# KEYPAD.net
KiCad netlist of a schematic drawn in Altium Designer
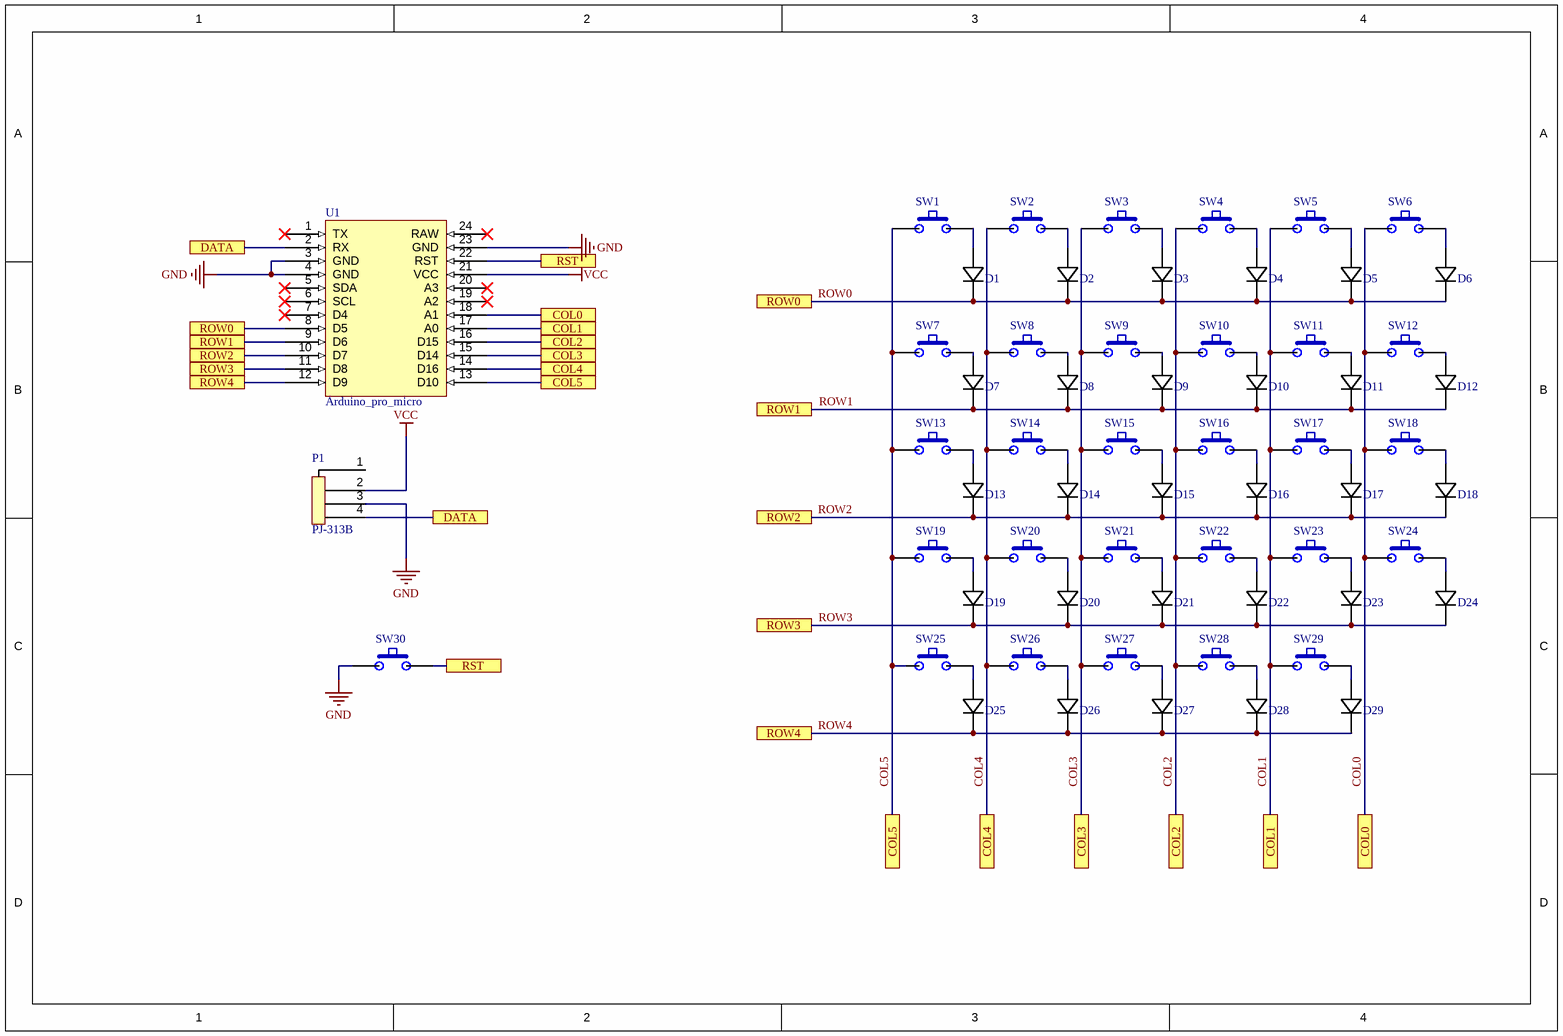
[diagram p0: KEYPAD.SchDoc]

(export (version "E")
  (design (tool "Eeschema 10.0.6"))
  (components
    (comp (ref "D1")
      (value "1N4148WSF-7")
      (footprint "DIOAD829W49L456D191")
      (description "No Description Available")
      (fields (field (name "COPYRIGHT") "Copyright (C) 2021 Ultra Librarian. All rights reserved."))
      (libsource (lib "lib") (part "1N4148WSF-7"))
    )
    (comp (ref "D2")
      (value "1N4148WSF-7")
      (footprint "DIOAD829W49L456D191")
      (description "No Description Available")
      (fields (field (name "COPYRIGHT") "Copyright (C) 2021 Ultra Librarian. All rights reserved."))
      (libsource (lib "lib") (part "1N4148WSF-7"))
    )
    (comp (ref "D3")
      (value "1N4148WSF-7")
      (footprint "DIOAD829W49L456D191")
      (description "No Description Available")
      (fields (field (name "COPYRIGHT") "Copyright (C) 2021 Ultra Librarian. All rights reserved."))
      (libsource (lib "lib") (part "1N4148WSF-7"))
    )
    (comp (ref "D4")
      (value "1N4148WSF-7")
      (footprint "DIOAD829W49L456D191")
      (description "No Description Available")
      (fields (field (name "COPYRIGHT") "Copyright (C) 2021 Ultra Librarian. All rights reserved."))
      (libsource (lib "lib") (part "1N4148WSF-7"))
    )
    (comp (ref "D5")
      (value "1N4148WSF-7")
      (footprint "DIOAD829W49L456D191")
      (description "No Description Available")
      (fields (field (name "COPYRIGHT") "Copyright (C) 2021 Ultra Librarian. All rights reserved."))
      (libsource (lib "lib") (part "1N4148WSF-7"))
    )
    (comp (ref "D6")
      (value "1N4148WSF-7")
      (footprint "DIOAD829W49L456D191")
      (description "No Description Available")
      (fields (field (name "COPYRIGHT") "Copyright (C) 2021 Ultra Librarian. All rights reserved."))
      (libsource (lib "lib") (part "1N4148WSF-7"))
    )
    (comp (ref "D7")
      (value "1N4148WSF-7")
      (footprint "DIOAD829W49L456D191")
      (description "No Description Available")
      (fields (field (name "COPYRIGHT") "Copyright (C) 2021 Ultra Librarian. All rights reserved."))
      (libsource (lib "lib") (part "1N4148WSF-7"))
    )
    (comp (ref "D8")
      (value "1N4148WSF-7")
      (footprint "DIOAD829W49L456D191")
      (description "No Description Available")
      (fields (field (name "COPYRIGHT") "Copyright (C) 2021 Ultra Librarian. All rights reserved."))
      (libsource (lib "lib") (part "1N4148WSF-7"))
    )
    (comp (ref "D9")
      (value "1N4148WSF-7")
      (footprint "DIOAD829W49L456D191")
      (description "No Description Available")
      (fields (field (name "COPYRIGHT") "Copyright (C) 2021 Ultra Librarian. All rights reserved."))
      (libsource (lib "lib") (part "1N4148WSF-7"))
    )
    (comp (ref "D10")
      (value "1N4148WSF-7")
      (footprint "DIOAD829W49L456D191")
      (description "No Description Available")
      (fields (field (name "COPYRIGHT") "Copyright (C) 2021 Ultra Librarian. All rights reserved."))
      (libsource (lib "lib") (part "1N4148WSF-7"))
    )
    (comp (ref "D11")
      (value "1N4148WSF-7")
      (footprint "DIOAD829W49L456D191")
      (description "No Description Available")
      (fields (field (name "COPYRIGHT") "Copyright (C) 2021 Ultra Librarian. All rights reserved."))
      (libsource (lib "lib") (part "1N4148WSF-7"))
    )
    (comp (ref "D12")
      (value "1N4148WSF-7")
      (footprint "DIOAD829W49L456D191")
      (description "No Description Available")
      (fields (field (name "COPYRIGHT") "Copyright (C) 2021 Ultra Librarian. All rights reserved."))
      (libsource (lib "lib") (part "1N4148WSF-7"))
    )
    (comp (ref "D13")
      (value "1N4148WSF-7")
      (footprint "DIOAD829W49L456D191")
      (description "No Description Available")
      (fields (field (name "COPYRIGHT") "Copyright (C) 2021 Ultra Librarian. All rights reserved."))
      (libsource (lib "lib") (part "1N4148WSF-7"))
    )
    (comp (ref "D14")
      (value "1N4148WSF-7")
      (footprint "DIOAD829W49L456D191")
      (description "No Description Available")
      (fields (field (name "COPYRIGHT") "Copyright (C) 2021 Ultra Librarian. All rights reserved."))
      (libsource (lib "lib") (part "1N4148WSF-7"))
    )
    (comp (ref "D15")
      (value "1N4148WSF-7")
      (footprint "DIOAD829W49L456D191")
      (description "No Description Available")
      (fields (field (name "COPYRIGHT") "Copyright (C) 2021 Ultra Librarian. All rights reserved."))
      (libsource (lib "lib") (part "1N4148WSF-7"))
    )
    (comp (ref "D16")
      (value "1N4148WSF-7")
      (footprint "DIOAD829W49L456D191")
      (description "No Description Available")
      (fields (field (name "COPYRIGHT") "Copyright (C) 2021 Ultra Librarian. All rights reserved."))
      (libsource (lib "lib") (part "1N4148WSF-7"))
    )
    (comp (ref "D17")
      (value "1N4148WSF-7")
      (footprint "DIOAD829W49L456D191")
      (description "No Description Available")
      (fields (field (name "COPYRIGHT") "Copyright (C) 2021 Ultra Librarian. All rights reserved."))
      (libsource (lib "lib") (part "1N4148WSF-7"))
    )
    (comp (ref "D18")
      (value "1N4148WSF-7")
      (footprint "DIOAD829W49L456D191")
      (description "No Description Available")
      (fields (field (name "COPYRIGHT") "Copyright (C) 2021 Ultra Librarian. All rights reserved."))
      (libsource (lib "lib") (part "1N4148WSF-7"))
    )
    (comp (ref "D19")
      (value "1N4148WSF-7")
      (footprint "DIOAD829W49L456D191")
      (description "No Description Available")
      (fields (field (name "COPYRIGHT") "Copyright (C) 2021 Ultra Librarian. All rights reserved."))
      (libsource (lib "lib") (part "1N4148WSF-7"))
    )
    (comp (ref "D20")
      (value "1N4148WSF-7")
      (footprint "DIOAD829W49L456D191")
      (description "No Description Available")
      (fields (field (name "COPYRIGHT") "Copyright (C) 2021 Ultra Librarian. All rights reserved."))
      (libsource (lib "lib") (part "1N4148WSF-7"))
    )
    (comp (ref "D21")
      (value "1N4148WSF-7")
      (footprint "DIOAD829W49L456D191")
      (description "No Description Available")
      (fields (field (name "COPYRIGHT") "Copyright (C) 2021 Ultra Librarian. All rights reserved."))
      (libsource (lib "lib") (part "1N4148WSF-7"))
    )
    (comp (ref "D22")
      (value "1N4148WSF-7")
      (footprint "DIOAD829W49L456D191")
      (description "No Description Available")
      (fields (field (name "COPYRIGHT") "Copyright (C) 2021 Ultra Librarian. All rights reserved."))
      (libsource (lib "lib") (part "1N4148WSF-7"))
    )
    (comp (ref "D23")
      (value "1N4148WSF-7")
      (footprint "DIOAD829W49L456D191")
      (description "No Description Available")
      (fields (field (name "COPYRIGHT") "Copyright (C) 2021 Ultra Librarian. All rights reserved."))
      (libsource (lib "lib") (part "1N4148WSF-7"))
    )
    (comp (ref "D24")
      (value "1N4148WSF-7")
      (footprint "DIOAD829W49L456D191")
      (description "No Description Available")
      (fields (field (name "COPYRIGHT") "Copyright (C) 2021 Ultra Librarian. All rights reserved."))
      (libsource (lib "lib") (part "1N4148WSF-7"))
    )
    (comp (ref "D25")
      (value "1N4148WSF-7")
      (footprint "DIOAD829W49L456D191")
      (description "No Description Available")
      (fields (field (name "COPYRIGHT") "Copyright (C) 2021 Ultra Librarian. All rights reserved."))
      (libsource (lib "lib") (part "1N4148WSF-7"))
    )
    (comp (ref "D26")
      (value "1N4148WSF-7")
      (footprint "DIOAD829W49L456D191")
      (description "No Description Available")
      (fields (field (name "COPYRIGHT") "Copyright (C) 2021 Ultra Librarian. All rights reserved."))
      (libsource (lib "lib") (part "1N4148WSF-7"))
    )
    (comp (ref "D27")
      (value "1N4148WSF-7")
      (footprint "DIOAD829W49L456D191")
      (description "No Description Available")
      (fields (field (name "COPYRIGHT") "Copyright (C) 2021 Ultra Librarian. All rights reserved."))
      (libsource (lib "lib") (part "1N4148WSF-7"))
    )
    (comp (ref "D28")
      (value "1N4148WSF-7")
      (footprint "DIOAD829W49L456D191")
      (description "No Description Available")
      (fields (field (name "COPYRIGHT") "Copyright (C) 2021 Ultra Librarian. All rights reserved."))
      (libsource (lib "lib") (part "1N4148WSF-7"))
    )
    (comp (ref "D29")
      (value "1N4148WSF-7")
      (footprint "DIOAD829W49L456D191")
      (description "No Description Available")
      (fields (field (name "COPYRIGHT") "Copyright (C) 2021 Ultra Librarian. All rights reserved."))
      (libsource (lib "lib") (part "1N4148WSF-7"))
    )
    (comp (ref "P1") (value "PJ-313B") (footprint "pj-313b6-x") (libsource (lib "lib") (part "PJ-313B")))
    (comp (ref "SW1") (value "~") (footprint "cherry_sw_double_side") (libsource (lib "lib") (part "SW")))
    (comp (ref "SW2") (value "~") (footprint "cherry_sw_double_side") (libsource (lib "lib") (part "SW")))
    (comp (ref "SW3") (value "~") (footprint "cherry_sw_double_side") (libsource (lib "lib") (part "SW")))
    (comp (ref "SW4") (value "~") (footprint "cherry_sw_double_side") (libsource (lib "lib") (part "SW")))
    (comp (ref "SW5") (value "~") (footprint "cherry_sw_double_side") (libsource (lib "lib") (part "SW")))
    (comp (ref "SW6") (value "~") (footprint "cherry_sw_double_side") (libsource (lib "lib") (part "SW")))
    (comp (ref "SW7") (value "~") (footprint "cherry_sw_double_side") (libsource (lib "lib") (part "SW")))
    (comp (ref "SW8") (value "~") (footprint "cherry_sw_double_side") (libsource (lib "lib") (part "SW")))
    (comp (ref "SW9") (value "~") (footprint "cherry_sw_double_side") (libsource (lib "lib") (part "SW")))
    (comp (ref "SW10") (value "~") (footprint "cherry_sw_double_side") (libsource (lib "lib") (part "SW")))
    (comp (ref "SW11") (value "~") (footprint "cherry_sw_double_side") (libsource (lib "lib") (part "SW")))
    (comp (ref "SW12") (value "~") (footprint "cherry_sw_double_side") (libsource (lib "lib") (part "SW")))
    (comp (ref "SW13") (value "~") (footprint "cherry_sw_double_side") (libsource (lib "lib") (part "SW")))
    (comp (ref "SW14") (value "~") (footprint "cherry_sw_double_side") (libsource (lib "lib") (part "SW")))
    (comp (ref "SW15") (value "~") (footprint "cherry_sw_double_side") (libsource (lib "lib") (part "SW")))
    (comp (ref "SW16") (value "~") (footprint "cherry_sw_double_side") (libsource (lib "lib") (part "SW")))
    (comp (ref "SW17") (value "~") (footprint "cherry_sw_double_side") (libsource (lib "lib") (part "SW")))
    (comp (ref "SW18") (value "~") (footprint "cherry_sw_double_side") (libsource (lib "lib") (part "SW")))
    (comp (ref "SW19") (value "~") (footprint "cherry_sw_double_side") (libsource (lib "lib") (part "SW")))
    (comp (ref "SW20") (value "~") (footprint "cherry_sw_double_side") (libsource (lib "lib") (part "SW")))
    (comp (ref "SW21") (value "~") (footprint "cherry_sw_double_side") (libsource (lib "lib") (part "SW")))
    (comp (ref "SW22") (value "~") (footprint "cherry_sw_double_side") (libsource (lib "lib") (part "SW")))
    (comp (ref "SW23") (value "~") (footprint "cherry_sw_double_side") (libsource (lib "lib") (part "SW")))
    (comp (ref "SW24") (value "~") (footprint "cherry_sw_double_side") (libsource (lib "lib") (part "SW")))
    (comp (ref "SW25") (value "~") (footprint "cherry_sw_double_side") (libsource (lib "lib") (part "SW")))
    (comp (ref "SW26") (value "~") (footprint "cherry_sw_double_side") (libsource (lib "lib") (part "SW")))
    (comp (ref "SW27") (value "~") (footprint "cherry_sw_double_side") (libsource (lib "lib") (part "SW")))
    (comp (ref "SW28") (value "~") (footprint "cherry_sw_double_side") (libsource (lib "lib") (part "SW")))
    (comp (ref "SW29") (value "~") (footprint "cherry_sw_double_side") (libsource (lib "lib") (part "SW")))
    (comp (ref "SW30") (value "~") (footprint "DTS-32") (libsource (lib "lib") (part "SW")))
    (comp (ref "U1")
      (value "Arduino_pro_micro")
      (footprint "Arduino_pro_micro")
      (libsource (lib "lib") (part "Arduino_pro_micro"))
    )
  )
  (nets
    (net (code "1") (name "/COL0") (class "Default")
      (node (ref "SW12") (pin "1") (pinfunction "1_1") (pintype "passive"))
      (node (ref "SW18") (pin "1") (pinfunction "1_1") (pintype "passive"))
      (node (ref "SW24") (pin "1") (pinfunction "1_1") (pintype "passive"))
      (node (ref "SW6") (pin "1") (pinfunction "1_1") (pintype "passive"))
      (node (ref "U1") (pin "18") (pinfunction "A1_18") (pintype "input"))
    )
    (net (code "2") (name "/COL1") (class "Default")
      (node (ref "SW11") (pin "1") (pinfunction "1_1") (pintype "passive"))
      (node (ref "SW17") (pin "1") (pinfunction "1_1") (pintype "passive"))
      (node (ref "SW23") (pin "1") (pinfunction "1_1") (pintype "passive"))
      (node (ref "SW29") (pin "1") (pinfunction "1_1") (pintype "passive"))
      (node (ref "SW5") (pin "1") (pinfunction "1_1") (pintype "passive"))
      (node (ref "U1") (pin "17") (pinfunction "A0_17") (pintype "input"))
    )
    (net (code "3") (name "/COL2") (class "Default")
      (node (ref "SW10") (pin "1") (pinfunction "1_1") (pintype "passive"))
      (node (ref "SW16") (pin "1") (pinfunction "1_1") (pintype "passive"))
      (node (ref "SW22") (pin "1") (pinfunction "1_1") (pintype "passive"))
      (node (ref "SW28") (pin "1") (pinfunction "1_1") (pintype "passive"))
      (node (ref "SW4") (pin "1") (pinfunction "1_1") (pintype "passive"))
      (node (ref "U1") (pin "16") (pinfunction "D15_16") (pintype "input"))
    )
    (net (code "4") (name "/COL3") (class "Default")
      (node (ref "SW15") (pin "1") (pinfunction "1_1") (pintype "passive"))
      (node (ref "SW21") (pin "1") (pinfunction "1_1") (pintype "passive"))
      (node (ref "SW27") (pin "1") (pinfunction "1_1") (pintype "passive"))
      (node (ref "SW3") (pin "1") (pinfunction "1_1") (pintype "passive"))
      (node (ref "SW9") (pin "1") (pinfunction "1_1") (pintype "passive"))
      (node (ref "U1") (pin "15") (pinfunction "D14_15") (pintype "input"))
    )
    (net (code "5") (name "/COL4") (class "Default")
      (node (ref "SW14") (pin "1") (pinfunction "1_1") (pintype "passive"))
      (node (ref "SW2") (pin "1") (pinfunction "1_1") (pintype "passive"))
      (node (ref "SW20") (pin "1") (pinfunction "1_1") (pintype "passive"))
      (node (ref "SW26") (pin "1") (pinfunction "1_1") (pintype "passive"))
      (node (ref "SW8") (pin "1") (pinfunction "1_1") (pintype "passive"))
      (node (ref "U1") (pin "14") (pinfunction "D16_14") (pintype "input"))
    )
    (net (code "6") (name "/COL5") (class "Default")
      (node (ref "SW1") (pin "1") (pinfunction "1_1") (pintype "passive"))
      (node (ref "SW13") (pin "1") (pinfunction "1_1") (pintype "passive"))
      (node (ref "SW19") (pin "1") (pinfunction "1_1") (pintype "passive"))
      (node (ref "SW25") (pin "1") (pinfunction "1_1") (pintype "passive"))
      (node (ref "SW7") (pin "1") (pinfunction "1_1") (pintype "passive"))
      (node (ref "U1") (pin "13") (pinfunction "D10_13") (pintype "input"))
    )
    (net (code "7") (name "/DATA") (class "Default")
      (node (ref "P1") (pin "4") (pinfunction "4_4") (pintype "passive"))
      (node (ref "U1") (pin "2") (pinfunction "RX_2") (pintype "input"))
    )
    (net (code "8") (name "/ROW0") (class "Default")
      (node (ref "D1") (pin "1") (pinfunction "1_1") (pintype "passive"))
      (node (ref "D2") (pin "1") (pinfunction "1_1") (pintype "passive"))
      (node (ref "D3") (pin "1") (pinfunction "1_1") (pintype "passive"))
      (node (ref "D4") (pin "1") (pinfunction "1_1") (pintype "passive"))
      (node (ref "D5") (pin "1") (pinfunction "1_1") (pintype "passive"))
      (node (ref "D6") (pin "1") (pinfunction "1_1") (pintype "passive"))
      (node (ref "U1") (pin "8") (pinfunction "D5_8") (pintype "input"))
    )
    (net (code "9") (name "/ROW1") (class "Default")
      (node (ref "D10") (pin "1") (pinfunction "1_1") (pintype "passive"))
      (node (ref "D11") (pin "1") (pinfunction "1_1") (pintype "passive"))
      (node (ref "D12") (pin "1") (pinfunction "1_1") (pintype "passive"))
      (node (ref "D7") (pin "1") (pinfunction "1_1") (pintype "passive"))
      (node (ref "D8") (pin "1") (pinfunction "1_1") (pintype "passive"))
      (node (ref "D9") (pin "1") (pinfunction "1_1") (pintype "passive"))
      (node (ref "U1") (pin "9") (pinfunction "D6_9") (pintype "input"))
    )
    (net (code "10") (name "/ROW2") (class "Default")
      (node (ref "D13") (pin "1") (pinfunction "1_1") (pintype "passive"))
      (node (ref "D14") (pin "1") (pinfunction "1_1") (pintype "passive"))
      (node (ref "D15") (pin "1") (pinfunction "1_1") (pintype "passive"))
      (node (ref "D16") (pin "1") (pinfunction "1_1") (pintype "passive"))
      (node (ref "D17") (pin "1") (pinfunction "1_1") (pintype "passive"))
      (node (ref "D18") (pin "1") (pinfunction "1_1") (pintype "passive"))
      (node (ref "U1") (pin "10") (pinfunction "D7_10") (pintype "input"))
    )
    (net (code "11") (name "/ROW3") (class "Default")
      (node (ref "D19") (pin "1") (pinfunction "1_1") (pintype "passive"))
      (node (ref "D20") (pin "1") (pinfunction "1_1") (pintype "passive"))
      (node (ref "D21") (pin "1") (pinfunction "1_1") (pintype "passive"))
      (node (ref "D22") (pin "1") (pinfunction "1_1") (pintype "passive"))
      (node (ref "D23") (pin "1") (pinfunction "1_1") (pintype "passive"))
      (node (ref "D24") (pin "1") (pinfunction "1_1") (pintype "passive"))
      (node (ref "U1") (pin "11") (pinfunction "D8_11") (pintype "input"))
    )
    (net (code "12") (name "/ROW4") (class "Default")
      (node (ref "D25") (pin "1") (pinfunction "1_1") (pintype "passive"))
      (node (ref "D26") (pin "1") (pinfunction "1_1") (pintype "passive"))
      (node (ref "D27") (pin "1") (pinfunction "1_1") (pintype "passive"))
      (node (ref "D28") (pin "1") (pinfunction "1_1") (pintype "passive"))
      (node (ref "D29") (pin "1") (pinfunction "1_1") (pintype "passive"))
      (node (ref "U1") (pin "12") (pinfunction "D9_12") (pintype "input"))
    )
    (net (code "13") (name "/RST") (class "Default")
      (node (ref "SW30") (pin "2") (pinfunction "2_2") (pintype "passive"))
      (node (ref "U1") (pin "22") (pinfunction "RST_22") (pintype "input"))
    )
    (net (code "14") (name "GND") (class "Default")
      (node (ref "P1") (pin "3") (pinfunction "3_3") (pintype "passive"))
      (node (ref "SW30") (pin "1") (pinfunction "1_1") (pintype "passive"))
      (node (ref "U1") (pin "23") (pinfunction "GND_23") (pintype "input"))
      (node (ref "U1") (pin "3") (pinfunction "GND_3") (pintype "input"))
      (node (ref "U1") (pin "4") (pinfunction "GND_4") (pintype "input"))
    )
    (net (code "15") (name "Net-(D1-Pad2)") (class "Default")
      (node (ref "D1") (pin "2") (pinfunction "2_2") (pintype "passive"))
      (node (ref "SW1") (pin "2") (pinfunction "2_2") (pintype "passive"))
    )
    (net (code "16") (name "Net-(D2-Pad2)") (class "Default")
      (node (ref "D2") (pin "2") (pinfunction "2_2") (pintype "passive"))
      (node (ref "SW2") (pin "2") (pinfunction "2_2") (pintype "passive"))
    )
    (net (code "17") (name "Net-(D3-Pad2)") (class "Default")
      (node (ref "D3") (pin "2") (pinfunction "2_2") (pintype "passive"))
      (node (ref "SW3") (pin "2") (pinfunction "2_2") (pintype "passive"))
    )
    (net (code "18") (name "Net-(D4-Pad2)") (class "Default")
      (node (ref "D4") (pin "2") (pinfunction "2_2") (pintype "passive"))
      (node (ref "SW4") (pin "2") (pinfunction "2_2") (pintype "passive"))
    )
    (net (code "19") (name "Net-(D5-Pad2)") (class "Default")
      (node (ref "D5") (pin "2") (pinfunction "2_2") (pintype "passive"))
      (node (ref "SW5") (pin "2") (pinfunction "2_2") (pintype "passive"))
    )
    (net (code "20") (name "Net-(D6-Pad2)") (class "Default")
      (node (ref "D6") (pin "2") (pinfunction "2_2") (pintype "passive"))
      (node (ref "SW6") (pin "2") (pinfunction "2_2") (pintype "passive"))
    )
    (net (code "21") (name "Net-(D7-Pad2)") (class "Default")
      (node (ref "D7") (pin "2") (pinfunction "2_2") (pintype "passive"))
      (node (ref "SW7") (pin "2") (pinfunction "2_2") (pintype "passive"))
    )
    (net (code "22") (name "Net-(D8-Pad2)") (class "Default")
      (node (ref "D8") (pin "2") (pinfunction "2_2") (pintype "passive"))
      (node (ref "SW8") (pin "2") (pinfunction "2_2") (pintype "passive"))
    )
    (net (code "23") (name "Net-(D9-Pad2)") (class "Default")
      (node (ref "D9") (pin "2") (pinfunction "2_2") (pintype "passive"))
      (node (ref "SW9") (pin "2") (pinfunction "2_2") (pintype "passive"))
    )
    (net (code "24") (name "Net-(D10-Pad2)") (class "Default")
      (node (ref "D10") (pin "2") (pinfunction "2_2") (pintype "passive"))
      (node (ref "SW10") (pin "2") (pinfunction "2_2") (pintype "passive"))
    )
    (net (code "25") (name "Net-(D11-Pad2)") (class "Default")
      (node (ref "D11") (pin "2") (pinfunction "2_2") (pintype "passive"))
      (node (ref "SW11") (pin "2") (pinfunction "2_2") (pintype "passive"))
    )
    (net (code "26") (name "Net-(D12-Pad2)") (class "Default")
      (node (ref "D12") (pin "2") (pinfunction "2_2") (pintype "passive"))
      (node (ref "SW12") (pin "2") (pinfunction "2_2") (pintype "passive"))
    )
    (net (code "27") (name "Net-(D13-Pad2)") (class "Default")
      (node (ref "D13") (pin "2") (pinfunction "2_2") (pintype "passive"))
      (node (ref "SW13") (pin "2") (pinfunction "2_2") (pintype "passive"))
    )
    (net (code "28") (name "Net-(D14-Pad2)") (class "Default")
      (node (ref "D14") (pin "2") (pinfunction "2_2") (pintype "passive"))
      (node (ref "SW14") (pin "2") (pinfunction "2_2") (pintype "passive"))
    )
    (net (code "29") (name "Net-(D15-Pad2)") (class "Default")
      (node (ref "D15") (pin "2") (pinfunction "2_2") (pintype "passive"))
      (node (ref "SW15") (pin "2") (pinfunction "2_2") (pintype "passive"))
    )
    (net (code "30") (name "Net-(D16-Pad2)") (class "Default")
      (node (ref "D16") (pin "2") (pinfunction "2_2") (pintype "passive"))
      (node (ref "SW16") (pin "2") (pinfunction "2_2") (pintype "passive"))
    )
    (net (code "31") (name "Net-(D17-Pad2)") (class "Default")
      (node (ref "D17") (pin "2") (pinfunction "2_2") (pintype "passive"))
      (node (ref "SW17") (pin "2") (pinfunction "2_2") (pintype "passive"))
    )
    (net (code "32") (name "Net-(D18-Pad2)") (class "Default")
      (node (ref "D18") (pin "2") (pinfunction "2_2") (pintype "passive"))
      (node (ref "SW18") (pin "2") (pinfunction "2_2") (pintype "passive"))
    )
    (net (code "33") (name "Net-(D19-Pad2)") (class "Default")
      (node (ref "D19") (pin "2") (pinfunction "2_2") (pintype "passive"))
      (node (ref "SW19") (pin "2") (pinfunction "2_2") (pintype "passive"))
    )
    (net (code "34") (name "Net-(D20-Pad2)") (class "Default")
      (node (ref "D20") (pin "2") (pinfunction "2_2") (pintype "passive"))
      (node (ref "SW20") (pin "2") (pinfunction "2_2") (pintype "passive"))
    )
    (net (code "35") (name "Net-(D21-Pad2)") (class "Default")
      (node (ref "D21") (pin "2") (pinfunction "2_2") (pintype "passive"))
      (node (ref "SW21") (pin "2") (pinfunction "2_2") (pintype "passive"))
    )
    (net (code "36") (name "Net-(D22-Pad2)") (class "Default")
      (node (ref "D22") (pin "2") (pinfunction "2_2") (pintype "passive"))
      (node (ref "SW22") (pin "2") (pinfunction "2_2") (pintype "passive"))
    )
    (net (code "37") (name "Net-(D23-Pad2)") (class "Default")
      (node (ref "D23") (pin "2") (pinfunction "2_2") (pintype "passive"))
      (node (ref "SW23") (pin "2") (pinfunction "2_2") (pintype "passive"))
    )
    (net (code "38") (name "Net-(D24-Pad2)") (class "Default")
      (node (ref "D24") (pin "2") (pinfunction "2_2") (pintype "passive"))
      (node (ref "SW24") (pin "2") (pinfunction "2_2") (pintype "passive"))
    )
    (net (code "39") (name "Net-(D25-Pad2)") (class "Default")
      (node (ref "D25") (pin "2") (pinfunction "2_2") (pintype "passive"))
      (node (ref "SW25") (pin "2") (pinfunction "2_2") (pintype "passive"))
    )
    (net (code "40") (name "Net-(D26-Pad2)") (class "Default")
      (node (ref "D26") (pin "2") (pinfunction "2_2") (pintype "passive"))
      (node (ref "SW26") (pin "2") (pinfunction "2_2") (pintype "passive"))
    )
    (net (code "41") (name "Net-(D27-Pad2)") (class "Default")
      (node (ref "D27") (pin "2") (pinfunction "2_2") (pintype "passive"))
      (node (ref "SW27") (pin "2") (pinfunction "2_2") (pintype "passive"))
    )
    (net (code "42") (name "Net-(D28-Pad2)") (class "Default")
      (node (ref "D28") (pin "2") (pinfunction "2_2") (pintype "passive"))
      (node (ref "SW28") (pin "2") (pinfunction "2_2") (pintype "passive"))
    )
    (net (code "43") (name "Net-(D29-Pad2)") (class "Default")
      (node (ref "D29") (pin "2") (pinfunction "2_2") (pintype "passive"))
      (node (ref "SW29") (pin "2") (pinfunction "2_2") (pintype "passive"))
    )
    (net (code "44") (name "VCC") (class "Default")
      (node (ref "P1") (pin "2") (pinfunction "2_2") (pintype "passive"))
      (node (ref "U1") (pin "21") (pinfunction "VCC_21") (pintype "input"))
    )
    (net (code "45") (name "unconnected-(P1-Pad1)") (class "Default")
      (node (ref "P1") (pin "1") (pinfunction "1_1") (pintype "passive"))
    )
    (net (code "46") (name "unconnected-(U1-A2-Pad19)") (class "Default")
      (node (ref "U1") (pin "19") (pinfunction "A2_19") (pintype "input+no_connect"))
    )
    (net (code "47") (name "unconnected-(U1-A3-Pad20)") (class "Default")
      (node (ref "U1") (pin "20") (pinfunction "A3_20") (pintype "input+no_connect"))
    )
    (net (code "48") (name "unconnected-(U1-D4-Pad7)") (class "Default")
      (node (ref "U1") (pin "7") (pinfunction "D4_7") (pintype "input+no_connect"))
    )
    (net (code "49") (name "unconnected-(U1-RAW-Pad24)") (class "Default")
      (node (ref "U1") (pin "24") (pinfunction "RAW_24") (pintype "input+no_connect"))
    )
    (net (code "50") (name "unconnected-(U1-SCL-Pad6)") (class "Default")
      (node (ref "U1") (pin "6") (pinfunction "SCL_6") (pintype "input+no_connect"))
    )
    (net (code "51") (name "unconnected-(U1-SDA-Pad5)") (class "Default")
      (node (ref "U1") (pin "5") (pinfunction "SDA_5") (pintype "input+no_connect"))
    )
    (net (code "52") (name "unconnected-(U1-TX-Pad1)") (class "Default")
      (node (ref "U1") (pin "1") (pinfunction "TX_1") (pintype "input+no_connect"))
    )
  )
)
